# PIN2DMD_Nucleo144.net
KiCad netlist of a schematic drawn in EAGLE
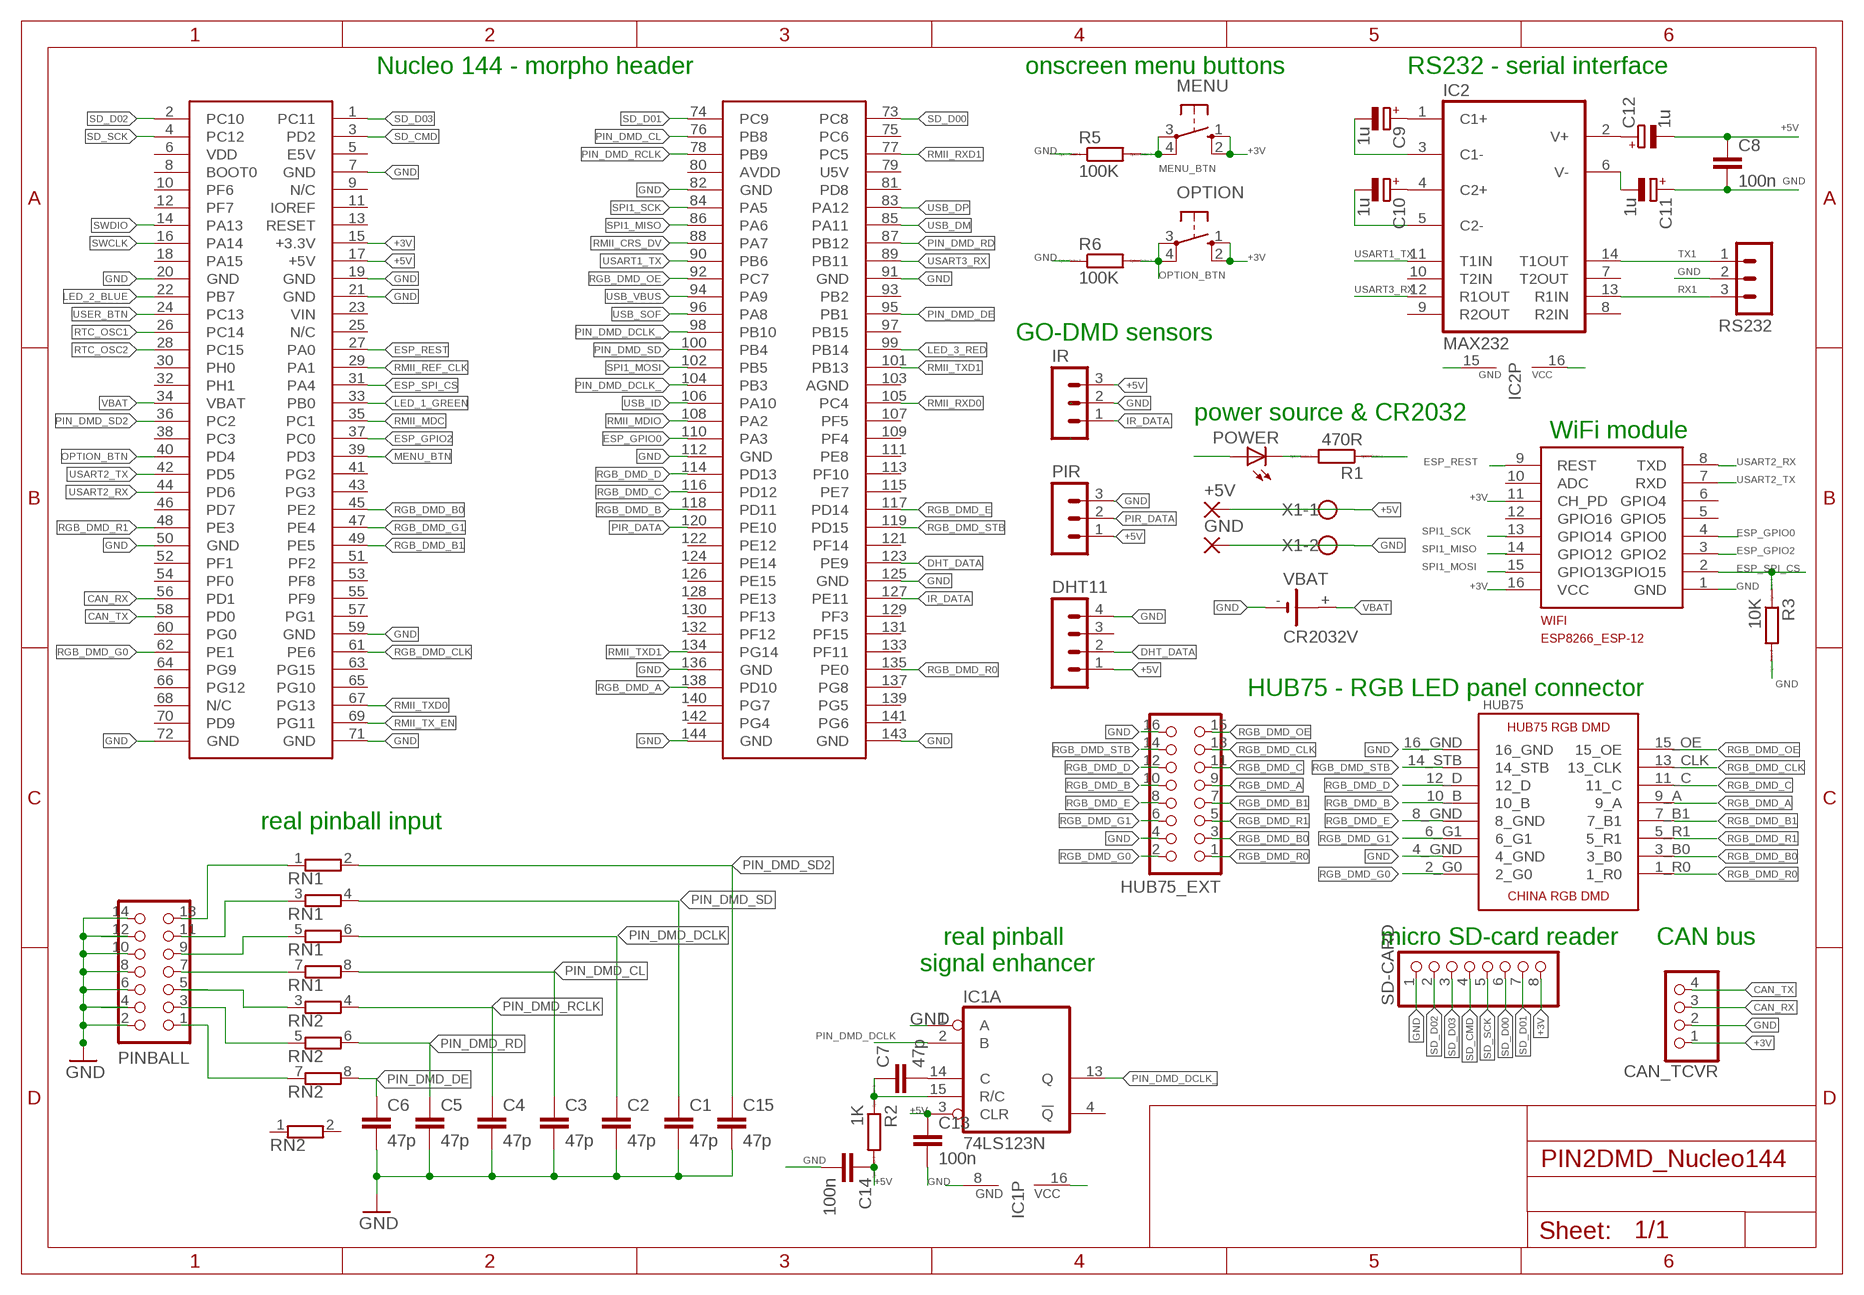
[diagram p0: schematic, sheet 1]

(export (version "E")
  (design (tool "Eeschema 10.0.6"))
  (components
    (comp (ref "+5V")
      (value "WIREPADSMD2,54-5,08")
      (footprint "eagle-import:SMD2,54-5,08")
      (libsource (lib "eagle-import") (part "WIREPADSMD2,54-5,08"))
    )
    (comp (ref "C1")
      (value "47p")
      (footprint "eagle-import:C025-024X044")
      (libsource (lib "eagle-import") (part "C-EU025-024X044"))
    )
    (comp (ref "C2")
      (value "47p")
      (footprint "eagle-import:C025-024X044")
      (libsource (lib "eagle-import") (part "C-EU025-024X044"))
    )
    (comp (ref "C3")
      (value "47p")
      (footprint "eagle-import:C025-024X044")
      (libsource (lib "eagle-import") (part "C-EU025-024X044"))
    )
    (comp (ref "C4")
      (value "47p")
      (footprint "eagle-import:C025-024X044")
      (libsource (lib "eagle-import") (part "C-EU025-024X044"))
    )
    (comp (ref "C5")
      (value "47p")
      (footprint "eagle-import:C025-024X044")
      (libsource (lib "eagle-import") (part "C-EU025-024X044"))
    )
    (comp (ref "C6")
      (value "47p")
      (footprint "eagle-import:C025-024X044")
      (libsource (lib "eagle-import") (part "C-EU025-024X044"))
    )
    (comp (ref "C7")
      (value "47p")
      (footprint "eagle-import:C025-024X044")
      (libsource (lib "eagle-import") (part "C-EU025-024X044"))
    )
    (comp (ref "C8")
      (value "100n")
      (footprint "eagle-import:C025-024X044")
      (libsource (lib "eagle-import") (part "C-EU025-024X044"))
    )
    (comp (ref "C9")
      (value "1u")
      (footprint "eagle-import:E2-4")
      (libsource (lib "eagle-import") (part "CPOL-EUE2-4"))
    )
    (comp (ref "C10")
      (value "1u")
      (footprint "eagle-import:E2-4")
      (libsource (lib "eagle-import") (part "CPOL-EUE2-4"))
    )
    (comp (ref "C11")
      (value "1u")
      (footprint "eagle-import:E2-4")
      (libsource (lib "eagle-import") (part "CPOL-EUE2-4"))
    )
    (comp (ref "C12")
      (value "1u")
      (footprint "eagle-import:E2-4")
      (libsource (lib "eagle-import") (part "CPOL-EUE2-4"))
    )
    (comp (ref "C13")
      (value "100n")
      (footprint "eagle-import:C025-024X044")
      (libsource (lib "eagle-import") (part "C-EU025-024X044"))
    )
    (comp (ref "C14")
      (value "100n")
      (footprint "eagle-import:C025-024X044")
      (libsource (lib "eagle-import") (part "C-EU025-024X044"))
    )
    (comp (ref "C15")
      (value "47p")
      (footprint "eagle-import:C025-024X044")
      (libsource (lib "eagle-import") (part "C-EU025-024X044"))
    )
    (comp (ref "CAN_TCVR")
      (value "PINHD-1X4")
      (footprint "eagle-import:1X04")
      (libsource (lib "eagle-import") (part "PINHD-1X4"))
    )
    (comp (ref "DHT11")
      (value "MA04-1")
      (footprint "eagle-import:MA04-1")
      (libsource (lib "eagle-import") (part "MA04-1"))
    )
    (comp (ref "GND")
      (value "WIREPADSMD2,54-5,08")
      (footprint "eagle-import:SMD2,54-5,08")
      (libsource (lib "eagle-import") (part "WIREPADSMD2,54-5,08"))
    )
    (comp (ref "HUB75")
      (value "RGB_DMD_HUB75_HEADER_FEMALE")
      (footprint "eagle-import:16_PIN_HUB75_RGB_FEMALE_DOWN")
      (libsource (lib "eagle-import") (part "RGB_DMD_HUB75_HEADER_FEMALE"))
    )
    (comp (ref "HUB75_EXT")
      (value "CON_HEADER_2X08B")
      (footprint "eagle-import:PINSHRD_PTH_2X08")
      (libsource (lib "eagle-import") (part "CON_HEADER_2X08B"))
    )
    (comp (ref "IC1")
      (value "74LS123N")
      (footprint "eagle-import:DIL16")
      (libsource (lib "eagle-import") (part "74123NLS"))
    )
    (comp (ref "IC2")
      (value "MAX232")
      (footprint "eagle-import:DIL16")
      (fields (field (name "MF") "MAXIM") (field (name "MPN") "MAX232ACPE+"))
      (libsource (lib "eagle-import") (part "MAX232"))
    )
    (comp (ref "IR")
      (value "MA03-1")
      (footprint "eagle-import:MA03-1")
      (libsource (lib "eagle-import") (part "MA03-1"))
    )
    (comp (ref "MENU")
      (value "10-XX")
      (footprint "eagle-import:B3F-10XX")
      (fields (field (name "MPN") "B3F-1000"))
      (libsource (lib "eagle-import") (part "10-XX"))
    )
    (comp (ref "OPTION")
      (value "10-XX")
      (footprint "eagle-import:B3F-10XX")
      (fields (field (name "MPN") "B3F-1000"))
      (libsource (lib "eagle-import") (part "10-XX"))
    )
    (comp (ref "PINBALL")
      (value "CON_HEADER_2X07-PTH-SHROUDED")
      (footprint "eagle-import:PINSHRD_PTH_2X07")
      (libsource (lib "eagle-import") (part "CON_HEADER_2X07-PTH-SHROUDED"))
    )
    (comp (ref "PIR")
      (value "MA03-1")
      (footprint "eagle-import:MA03-1")
      (libsource (lib "eagle-import") (part "MA03-1"))
    )
    (comp (ref "POWER")
      (value "LED3MM")
      (footprint "eagle-import:LED3MM")
      (libsource (lib "eagle-import") (part "LED3MM"))
    )
    (comp (ref "R1")
      (value "470R")
      (footprint "eagle-import:0207_10")
      (libsource (lib "eagle-import") (part "R0207/10"))
    )
    (comp (ref "R2")
      (value "1K")
      (footprint "eagle-import:0207_10")
      (libsource (lib "eagle-import") (part "R0207/10"))
    )
    (comp (ref "R3")
      (value "10K")
      (footprint "eagle-import:0207_10")
      (libsource (lib "eagle-import") (part "R0207/10"))
    )
    (comp (ref "R5")
      (value "100K")
      (footprint "eagle-import:0207_10")
      (libsource (lib "eagle-import") (part "R0207/10"))
    )
    (comp (ref "R6")
      (value "100K")
      (footprint "eagle-import:0207_10")
      (libsource (lib "eagle-import") (part "R0207/10"))
    )
    (comp (ref "RN1")
      (value "E4RP")
      (footprint "eagle-import:SIL8")
      (libsource (lib "eagle-import") (part "E4RP"))
    )
    (comp (ref "RN2")
      (value "E4RP")
      (footprint "eagle-import:SIL8")
      (libsource (lib "eagle-import") (part "E4RP"))
    )
    (comp (ref "RS232")
      (value "MA03-1")
      (footprint "eagle-import:MA03-1")
      (libsource (lib "eagle-import") (part "MA03-1"))
    )
    (comp (ref "SD-CARD")
      (value "PINHD-1X8")
      (footprint "eagle-import:1X08")
      (libsource (lib "eagle-import") (part "PINHD-1X8"))
    )
    (comp (ref "U$1")
      (value "NUCLEO-144")
      (footprint "eagle-import:NUCLEO-144")
      (libsource (lib "eagle-import") (part "NUCLEO-144"))
    )
    (comp (ref "VBAT")
      (value "CR2032V")
      (footprint "eagle-import:CR2032V")
      (libsource (lib "eagle-import") (part "CR2032V"))
    )
    (comp (ref "WIFI")
      (value "ESP8266_ESP-12")
      (footprint "eagle-import:ESP8266-ESP12")
      (libsource (lib "eagle-import") (part "ESP8266_ESP-12"))
    )
    (comp (ref "X1")
      (value "W237-102")
      (footprint "eagle-import:W237-102")
      (fields (field (name "MPN") "237-102"))
      (libsource (lib "eagle-import") (part "W237-102"))
    )
  )
  (nets
    (net (code "1") (name "+3V") (class "Default")
      (node (ref "CAN_TCVR") (pin "1") (pinfunction "1_1") (pintype "passive"))
      (node (ref "MENU") (pin "1") (pinfunction "S_1") (pintype "passive"))
      (node (ref "MENU") (pin "2") (pinfunction "S1_2") (pintype "passive"))
      (node (ref "OPTION") (pin "1") (pinfunction "S_1") (pintype "passive"))
      (node (ref "OPTION") (pin "2") (pinfunction "S1_2") (pintype "passive"))
      (node (ref "SD-CARD") (pin "8") (pinfunction "8_8") (pintype "passive"))
      (node (ref "U$1") (pin "15") (pinfunction "+3.3V_15") (pintype "bidirectional"))
      (node (ref "WIFI") (pin "11") (pinfunction "CH_PD_11") (pintype "bidirectional"))
      (node (ref "WIFI") (pin "16") (pinfunction "VCC_16") (pintype "bidirectional"))
    )
    (net (code "2") (name "+5V") (class "Default")
      (node (ref "+5V") (pin "1") (pinfunction "P_1") (pintype "passive"))
      (node (ref "C12") (pin "-") (pinfunction "-_-") (pintype "passive"))
      (node (ref "C13") (pin "1") (pinfunction "1_1") (pintype "passive"))
      (node (ref "C14") (pin "1") (pinfunction "1_1") (pintype "passive"))
      (node (ref "C8") (pin "1") (pinfunction "1_1") (pintype "passive"))
      (node (ref "DHT11") (pin "1") (pinfunction "1_1") (pintype "passive"))
      (node (ref "IC1") (pin "16") (pinfunction "VCC_16") (pintype "power_in"))
      (node (ref "IC1") (pin "3") (pinfunction "CLR_3") (pintype "input"))
      (node (ref "IC2") (pin "16") (pinfunction "VCC_16") (pintype "power_in"))
      (node (ref "IR") (pin "3") (pinfunction "3_3") (pintype "passive"))
      (node (ref "PIR") (pin "1") (pinfunction "1_1") (pintype "passive"))
      (node (ref "POWER") (pin "A") (pinfunction "A_A") (pintype "passive"))
      (node (ref "R2") (pin "2") (pinfunction "2_2") (pintype "passive"))
      (node (ref "U$1") (pin "17") (pinfunction "+5V_17") (pintype "bidirectional"))
      (node (ref "X1") (pin "1") (pinfunction "KL_1") (pintype "passive"))
    )
    (net (code "3") (name "/RX1") (class "Default")
      (node (ref "IC2") (pin "13") (pinfunction "R1IN_13") (pintype "input"))
      (node (ref "RS232") (pin "3") (pinfunction "3_3") (pintype "passive"))
    )
    (net (code "4") (name "/TX1") (class "Default")
      (node (ref "IC2") (pin "14") (pinfunction "T1OUT_14") (pintype "output"))
      (node (ref "RS232") (pin "1") (pinfunction "1_1") (pintype "passive"))
    )
    (net (code "5") (name "CAN_RX") (class "Default")
      (node (ref "CAN_TCVR") (pin "3") (pinfunction "3_3") (pintype "passive"))
      (node (ref "U$1") (pin "56") (pinfunction "PD1_56") (pintype "bidirectional"))
    )
    (net (code "6") (name "CAN_TX") (class "Default")
      (node (ref "CAN_TCVR") (pin "4") (pinfunction "4_4") (pintype "passive"))
      (node (ref "U$1") (pin "58") (pinfunction "PD0_58") (pintype "bidirectional"))
    )
    (net (code "7") (name "DHT_DATA") (class "Default")
      (node (ref "DHT11") (pin "2") (pinfunction "2_2") (pintype "passive"))
      (node (ref "U$1") (pin "123") (pinfunction "PE9_123") (pintype "bidirectional"))
    )
    (net (code "8") (name "ESP_GPIO0") (class "Default")
      (node (ref "U$1") (pin "110") (pinfunction "PA3_110") (pintype "bidirectional"))
      (node (ref "WIFI") (pin "4") (pinfunction "GPIO0_4") (pintype "bidirectional"))
    )
    (net (code "9") (name "ESP_GPIO2") (class "Default")
      (node (ref "U$1") (pin "37") (pinfunction "PC0_37") (pintype "bidirectional"))
      (node (ref "WIFI") (pin "3") (pinfunction "GPIO2_3") (pintype "bidirectional"))
    )
    (net (code "10") (name "ESP_REST") (class "Default")
      (node (ref "U$1") (pin "27") (pinfunction "PA0_27") (pintype "bidirectional"))
      (node (ref "WIFI") (pin "9") (pinfunction "REST_9") (pintype "bidirectional"))
    )
    (net (code "11") (name "ESP_SPI_CS") (class "Default")
      (node (ref "R3") (pin "1") (pinfunction "1_1") (pintype "passive"))
      (node (ref "U$1") (pin "31") (pinfunction "PA4_31") (pintype "bidirectional"))
      (node (ref "WIFI") (pin "2") (pinfunction "GPIO15_2") (pintype "bidirectional"))
    )
    (net (code "12") (name "GND") (class "Default")
      (node (ref "C1") (pin "2") (pinfunction "2_2") (pintype "passive"))
      (node (ref "C11") (pin "+") (pinfunction "+_+") (pintype "passive"))
      (node (ref "C13") (pin "2") (pinfunction "2_2") (pintype "passive"))
      (node (ref "C14") (pin "2") (pinfunction "2_2") (pintype "passive"))
      (node (ref "C15") (pin "2") (pinfunction "2_2") (pintype "passive"))
      (node (ref "C2") (pin "2") (pinfunction "2_2") (pintype "passive"))
      (node (ref "C3") (pin "2") (pinfunction "2_2") (pintype "passive"))
      (node (ref "C4") (pin "2") (pinfunction "2_2") (pintype "passive"))
      (node (ref "C5") (pin "2") (pinfunction "2_2") (pintype "passive"))
      (node (ref "C6") (pin "2") (pinfunction "2_2") (pintype "passive"))
      (node (ref "C8") (pin "2") (pinfunction "2_2") (pintype "passive"))
      (node (ref "CAN_TCVR") (pin "2") (pinfunction "2_2") (pintype "passive"))
      (node (ref "DHT11") (pin "4") (pinfunction "4_4") (pintype "passive"))
      (node (ref "GND") (pin "1") (pinfunction "P_1") (pintype "passive"))
      (node (ref "HUB75") (pin "16_GND") (pinfunction "16_GND_16_GND") (pintype "bidirectional"))
      (node (ref "HUB75") (pin "4_GND") (pinfunction "4_GND_4_GND") (pintype "bidirectional"))
      (node (ref "HUB75_EXT") (pin "16") (pinfunction "16_16") (pintype "passive"))
      (node (ref "HUB75_EXT") (pin "4") (pinfunction "4_4") (pintype "passive"))
      (node (ref "IC1") (pin "1") (pinfunction "A_1") (pintype "input"))
      (node (ref "IC1") (pin "8") (pinfunction "GND_8") (pintype "power_in"))
      (node (ref "IC2") (pin "15") (pinfunction "GND_15") (pintype "power_in"))
      (node (ref "IR") (pin "2") (pinfunction "2_2") (pintype "passive"))
      (node (ref "PINBALL") (pin "10") (pinfunction "10_10") (pintype "passive"))
      (node (ref "PINBALL") (pin "12") (pinfunction "12_12") (pintype "passive"))
      (node (ref "PINBALL") (pin "14") (pinfunction "14_14") (pintype "passive"))
      (node (ref "PINBALL") (pin "2") (pinfunction "2_2") (pintype "passive"))
      (node (ref "PINBALL") (pin "4") (pinfunction "4_4") (pintype "passive"))
      (node (ref "PINBALL") (pin "6") (pinfunction "6_6") (pintype "passive"))
      (node (ref "PINBALL") (pin "8") (pinfunction "8_8") (pintype "passive"))
      (node (ref "PIR") (pin "3") (pinfunction "3_3") (pintype "passive"))
      (node (ref "R1") (pin "1") (pinfunction "1_1") (pintype "passive"))
      (node (ref "R3") (pin "2") (pinfunction "2_2") (pintype "passive"))
      (node (ref "R5") (pin "1") (pinfunction "1_1") (pintype "passive"))
      (node (ref "R6") (pin "1") (pinfunction "1_1") (pintype "passive"))
      (node (ref "RS232") (pin "2") (pinfunction "2_2") (pintype "passive"))
      (node (ref "SD-CARD") (pin "1") (pinfunction "1_1") (pintype "passive"))
      (node (ref "U$1") (pin "112") (pinfunction "GND_112") (pintype "bidirectional"))
      (node (ref "U$1") (pin "125") (pinfunction "GND_125") (pintype "bidirectional"))
      (node (ref "U$1") (pin "136") (pinfunction "GND_136") (pintype "bidirectional"))
      (node (ref "U$1") (pin "143") (pinfunction "GND_143") (pintype "bidirectional"))
      (node (ref "U$1") (pin "144") (pinfunction "GND_144") (pintype "bidirectional"))
      (node (ref "U$1") (pin "19") (pinfunction "GND_19") (pintype "bidirectional"))
      (node (ref "U$1") (pin "20") (pinfunction "GND_20") (pintype "bidirectional"))
      (node (ref "U$1") (pin "21") (pinfunction "GND_21") (pintype "bidirectional"))
      (node (ref "U$1") (pin "50") (pinfunction "GND_50") (pintype "bidirectional"))
      (node (ref "U$1") (pin "59") (pinfunction "GND_59") (pintype "bidirectional"))
      (node (ref "U$1") (pin "7") (pinfunction "GND_7") (pintype "bidirectional"))
      (node (ref "U$1") (pin "71") (pinfunction "GND_71") (pintype "bidirectional"))
      (node (ref "U$1") (pin "72") (pinfunction "GND_72") (pintype "bidirectional"))
      (node (ref "U$1") (pin "82") (pinfunction "GND_82") (pintype "bidirectional"))
      (node (ref "U$1") (pin "91") (pinfunction "GND_91") (pintype "bidirectional"))
      (node (ref "VBAT") (pin "-") (pinfunction "-_-") (pintype "passive"))
      (node (ref "WIFI") (pin "1") (pinfunction "GND_1") (pintype "bidirectional"))
      (node (ref "X1") (pin "2") (pinfunction "KL_2") (pintype "passive"))
    )
    (net (code "13") (name "IR_DATA") (class "Default")
      (node (ref "IR") (pin "1") (pinfunction "1_1") (pintype "passive"))
      (node (ref "U$1") (pin "127") (pinfunction "PE11_127") (pintype "bidirectional"))
    )
    (net (code "14") (name "LED_1_GREEN") (class "Default")
      (node (ref "U$1") (pin "33") (pinfunction "PB0_33") (pintype "bidirectional"))
    )
    (net (code "15") (name "LED_2_BLUE") (class "Default")
      (node (ref "U$1") (pin "22") (pinfunction "PB7_22") (pintype "bidirectional"))
    )
    (net (code "16") (name "LED_3_RED") (class "Default")
      (node (ref "U$1") (pin "99") (pinfunction "PB14_99") (pintype "bidirectional"))
    )
    (net (code "17") (name "MENU_BTN") (class "Default")
      (node (ref "MENU") (pin "3") (pinfunction "P_3") (pintype "passive"))
      (node (ref "MENU") (pin "4") (pinfunction "P1_4") (pintype "passive"))
      (node (ref "R5") (pin "2") (pinfunction "2_2") (pintype "passive"))
      (node (ref "U$1") (pin "39") (pinfunction "PD3_39") (pintype "bidirectional"))
    )
    (net (code "18") (name "Net-(IC1A-C)") (class "Default")
      (node (ref "C7") (pin "2") (pinfunction "2_2") (pintype "passive"))
      (node (ref "IC1") (pin "14") (pinfunction "C_14") (pintype "input"))
    )
    (net (code "19") (name "Net-(IC1A-R{slash}C)") (class "Default")
      (node (ref "C7") (pin "1") (pinfunction "1_1") (pintype "passive"))
      (node (ref "IC1") (pin "15") (pinfunction "R/C_15") (pintype "input"))
      (node (ref "R2") (pin "1") (pinfunction "1_1") (pintype "passive"))
    )
    (net (code "20") (name "Net-(IC2A-C1+)") (class "Default")
      (node (ref "C9") (pin "+") (pinfunction "+_+") (pintype "passive"))
      (node (ref "IC2") (pin "1") (pinfunction "C1+_1") (pintype "bidirectional"))
    )
    (net (code "21") (name "Net-(IC2A-C1-)") (class "Default")
      (node (ref "C9") (pin "-") (pinfunction "-_-") (pintype "passive"))
      (node (ref "IC2") (pin "3") (pinfunction "C1-_3") (pintype "bidirectional"))
    )
    (net (code "22") (name "Net-(IC2A-C2+)") (class "Default")
      (node (ref "C10") (pin "+") (pinfunction "+_+") (pintype "passive"))
      (node (ref "IC2") (pin "4") (pinfunction "C2+_4") (pintype "bidirectional"))
    )
    (net (code "23") (name "Net-(IC2A-C2-)") (class "Default")
      (node (ref "C10") (pin "-") (pinfunction "-_-") (pintype "passive"))
      (node (ref "IC2") (pin "5") (pinfunction "C2-_5") (pintype "bidirectional"))
    )
    (net (code "24") (name "Net-(IC2A-V+)") (class "Default")
      (node (ref "C12") (pin "+") (pinfunction "+_+") (pintype "passive"))
      (node (ref "IC2") (pin "2") (pinfunction "V+_2") (pintype "bidirectional"))
    )
    (net (code "25") (name "Net-(IC2A-V-)") (class "Default")
      (node (ref "C11") (pin "-") (pinfunction "-_-") (pintype "passive"))
      (node (ref "IC2") (pin "6") (pinfunction "V-_6") (pintype "bidirectional"))
    )
    (net (code "26") (name "Net-(PINBALL-Pad13)") (class "Default")
      (node (ref "PINBALL") (pin "13") (pinfunction "13_13") (pintype "passive"))
      (node (ref "RN1") (pin "1") (pinfunction "1_1") (pintype "passive"))
    )
    (net (code "27") (name "Net-(POWER-C)") (class "Default")
      (node (ref "POWER") (pin "K") (pinfunction "C_K") (pintype "passive"))
      (node (ref "R1") (pin "2") (pinfunction "2_2") (pintype "passive"))
    )
    (net (code "28") (name "Net-(RN1B-1)") (class "Default")
      (node (ref "PINBALL") (pin "11") (pinfunction "11_11") (pintype "passive"))
      (node (ref "RN1") (pin "3") (pinfunction "1_3") (pintype "passive"))
    )
    (net (code "29") (name "Net-(RN1C-1)") (class "Default")
      (node (ref "PINBALL") (pin "9") (pinfunction "9_9") (pintype "passive"))
      (node (ref "RN1") (pin "5") (pinfunction "1_5") (pintype "passive"))
    )
    (net (code "30") (name "Net-(RN1D-1)") (class "Default")
      (node (ref "PINBALL") (pin "7") (pinfunction "7_7") (pintype "passive"))
      (node (ref "RN1") (pin "7") (pinfunction "1_7") (pintype "passive"))
    )
    (net (code "31") (name "Net-(RN2B-1)") (class "Default")
      (node (ref "PINBALL") (pin "5") (pinfunction "5_5") (pintype "passive"))
      (node (ref "RN2") (pin "3") (pinfunction "1_3") (pintype "passive"))
    )
    (net (code "32") (name "Net-(RN2C-1)") (class "Default")
      (node (ref "PINBALL") (pin "3") (pinfunction "3_3") (pintype "passive"))
      (node (ref "RN2") (pin "5") (pinfunction "1_5") (pintype "passive"))
    )
    (net (code "33") (name "Net-(RN2D-1)") (class "Default")
      (node (ref "PINBALL") (pin "1") (pinfunction "1_1") (pintype "passive"))
      (node (ref "RN2") (pin "7") (pinfunction "1_7") (pintype "passive"))
    )
    (net (code "34") (name "OPTION_BTN") (class "Default")
      (node (ref "OPTION") (pin "3") (pinfunction "P_3") (pintype "passive"))
      (node (ref "OPTION") (pin "4") (pinfunction "P1_4") (pintype "passive"))
      (node (ref "R6") (pin "2") (pinfunction "2_2") (pintype "passive"))
      (node (ref "U$1") (pin "40") (pinfunction "PD4_40") (pintype "bidirectional"))
    )
    (net (code "35") (name "PIN_DMD_CL") (class "Default")
      (node (ref "C3") (pin "1") (pinfunction "1_1") (pintype "passive"))
      (node (ref "RN1") (pin "8") (pinfunction "2_8") (pintype "passive"))
      (node (ref "U$1") (pin "76") (pinfunction "PB8_76") (pintype "bidirectional"))
    )
    (net (code "36") (name "PIN_DMD_DCLK") (class "Default")
      (node (ref "C2") (pin "1") (pinfunction "1_1") (pintype "passive"))
      (node (ref "IC1") (pin "2") (pinfunction "B_2") (pintype "input"))
      (node (ref "RN1") (pin "6") (pinfunction "2_6") (pintype "passive"))
    )
    (net (code "37") (name "PIN_DMD_DCLK_") (class "Default")
      (node (ref "IC1") (pin "13") (pinfunction "Q_13") (pintype "output"))
      (node (ref "U$1") (pin "104") (pinfunction "PB3_104") (pintype "bidirectional"))
      (node (ref "U$1") (pin "98") (pinfunction "PB10_98") (pintype "bidirectional"))
    )
    (net (code "38") (name "PIN_DMD_DE") (class "Default")
      (node (ref "C6") (pin "1") (pinfunction "1_1") (pintype "passive"))
      (node (ref "RN2") (pin "8") (pinfunction "2_8") (pintype "passive"))
      (node (ref "U$1") (pin "95") (pinfunction "PB1_95") (pintype "bidirectional"))
    )
    (net (code "39") (name "PIN_DMD_RCLK") (class "Default")
      (node (ref "C4") (pin "1") (pinfunction "1_1") (pintype "passive"))
      (node (ref "RN2") (pin "4") (pinfunction "2_4") (pintype "passive"))
      (node (ref "U$1") (pin "78") (pinfunction "PB9_78") (pintype "bidirectional"))
    )
    (net (code "40") (name "PIN_DMD_RD") (class "Default")
      (node (ref "C5") (pin "1") (pinfunction "1_1") (pintype "passive"))
      (node (ref "RN2") (pin "6") (pinfunction "2_6") (pintype "passive"))
      (node (ref "U$1") (pin "87") (pinfunction "PB12_87") (pintype "bidirectional"))
    )
    (net (code "41") (name "PIN_DMD_SD") (class "Default")
      (node (ref "C1") (pin "1") (pinfunction "1_1") (pintype "passive"))
      (node (ref "RN1") (pin "4") (pinfunction "2_4") (pintype "passive"))
      (node (ref "U$1") (pin "100") (pinfunction "PB4_100") (pintype "bidirectional"))
    )
    (net (code "42") (name "PIN_DMD_SD2") (class "Default")
      (node (ref "C15") (pin "1") (pinfunction "1_1") (pintype "passive"))
      (node (ref "RN1") (pin "2") (pinfunction "2_2") (pintype "passive"))
      (node (ref "U$1") (pin "36") (pinfunction "PC2_36") (pintype "bidirectional"))
    )
    (net (code "43") (name "PIR_DATA") (class "Default")
      (node (ref "PIR") (pin "2") (pinfunction "2_2") (pintype "passive"))
      (node (ref "U$1") (pin "120") (pinfunction "PE10_120") (pintype "bidirectional"))
    )
    (net (code "44") (name "RGB_DMD_A") (class "Default")
      (node (ref "HUB75") (pin "9_A") (pinfunction "9_A_9_A") (pintype "bidirectional"))
      (node (ref "HUB75_EXT") (pin "9") (pinfunction "9_9") (pintype "passive"))
      (node (ref "U$1") (pin "138") (pinfunction "PD10_138") (pintype "bidirectional"))
    )
    (net (code "45") (name "RGB_DMD_B") (class "Default")
      (node (ref "HUB75") (pin "10_B") (pinfunction "10_B_10_B") (pintype "bidirectional"))
      (node (ref "HUB75_EXT") (pin "10") (pinfunction "10_10") (pintype "passive"))
      (node (ref "U$1") (pin "118") (pinfunction "PD11_118") (pintype "bidirectional"))
    )
    (net (code "46") (name "RGB_DMD_B0") (class "Default")
      (node (ref "HUB75") (pin "3_B0") (pinfunction "3_B0_3_B0") (pintype "bidirectional"))
      (node (ref "HUB75_EXT") (pin "3") (pinfunction "3_3") (pintype "passive"))
      (node (ref "U$1") (pin "45") (pinfunction "PE2_45") (pintype "bidirectional"))
    )
    (net (code "47") (name "RGB_DMD_B1") (class "Default")
      (node (ref "HUB75") (pin "7_B1") (pinfunction "7_B1_7_B1") (pintype "bidirectional"))
      (node (ref "HUB75_EXT") (pin "7") (pinfunction "7_7") (pintype "passive"))
      (node (ref "U$1") (pin "49") (pinfunction "PE5_49") (pintype "bidirectional"))
    )
    (net (code "48") (name "RGB_DMD_C") (class "Default")
      (node (ref "HUB75") (pin "11_C") (pinfunction "11_C_11_C") (pintype "bidirectional"))
      (node (ref "HUB75_EXT") (pin "11") (pinfunction "11_11") (pintype "passive"))
      (node (ref "U$1") (pin "116") (pinfunction "PD12_116") (pintype "bidirectional"))
    )
    (net (code "49") (name "RGB_DMD_CLK") (class "Default")
      (node (ref "HUB75") (pin "13_CLK") (pinfunction "13_CLK_13_CLK") (pintype "bidirectional"))
      (node (ref "HUB75_EXT") (pin "13") (pinfunction "13_13") (pintype "passive"))
      (node (ref "U$1") (pin "61") (pinfunction "PE6_61") (pintype "bidirectional"))
    )
    (net (code "50") (name "RGB_DMD_D") (class "Default")
      (node (ref "HUB75") (pin "12_D") (pinfunction "12_D_12_D") (pintype "bidirectional"))
      (node (ref "HUB75_EXT") (pin "12") (pinfunction "12_12") (pintype "passive"))
      (node (ref "U$1") (pin "114") (pinfunction "PD13_114") (pintype "bidirectional"))
    )
    (net (code "51") (name "RGB_DMD_E") (class "Default")
      (node (ref "HUB75") (pin "8_GND") (pinfunction "8_GND_8_GND") (pintype "bidirectional"))
      (node (ref "HUB75_EXT") (pin "8") (pinfunction "8_8") (pintype "passive"))
      (node (ref "U$1") (pin "117") (pinfunction "PD14_117") (pintype "bidirectional"))
    )
    (net (code "52") (name "RGB_DMD_G0") (class "Default")
      (node (ref "HUB75") (pin "2_G0") (pinfunction "2_G0_2_G0") (pintype "bidirectional"))
      (node (ref "HUB75_EXT") (pin "2") (pinfunction "2_2") (pintype "passive"))
      (node (ref "U$1") (pin "62") (pinfunction "PE1_62") (pintype "bidirectional"))
    )
    (net (code "53") (name "RGB_DMD_G1") (class "Default")
      (node (ref "HUB75") (pin "6_G1") (pinfunction "6_G1_6_G1") (pintype "bidirectional"))
      (node (ref "HUB75_EXT") (pin "6") (pinfunction "6_6") (pintype "passive"))
      (node (ref "U$1") (pin "47") (pinfunction "PE4_47") (pintype "bidirectional"))
    )
    (net (code "54") (name "RGB_DMD_OE") (class "Default")
      (node (ref "HUB75") (pin "15_OE") (pinfunction "15_OE_15_OE") (pintype "bidirectional"))
      (node (ref "HUB75_EXT") (pin "15") (pinfunction "15_15") (pintype "passive"))
      (node (ref "U$1") (pin "92") (pinfunction "PC7_92") (pintype "bidirectional"))
    )
    (net (code "55") (name "RGB_DMD_R0") (class "Default")
      (node (ref "HUB75") (pin "1_R0") (pinfunction "1_R0_1_R0") (pintype "bidirectional"))
      (node (ref "HUB75_EXT") (pin "1") (pinfunction "1_1") (pintype "passive"))
      (node (ref "U$1") (pin "135") (pinfunction "PE0_135") (pintype "bidirectional"))
    )
    (net (code "56") (name "RGB_DMD_R1") (class "Default")
      (node (ref "HUB75") (pin "5_R1") (pinfunction "5_R1_5_R1") (pintype "bidirectional"))
      (node (ref "HUB75_EXT") (pin "5") (pinfunction "5_5") (pintype "passive"))
      (node (ref "U$1") (pin "48") (pinfunction "PE3_48") (pintype "bidirectional"))
    )
    (net (code "57") (name "RGB_DMD_STB") (class "Default")
      (node (ref "HUB75") (pin "14_STB") (pinfunction "14_STB_14_STB") (pintype "bidirectional"))
      (node (ref "HUB75_EXT") (pin "14") (pinfunction "14_14") (pintype "passive"))
      (node (ref "U$1") (pin "119") (pinfunction "PD15_119") (pintype "bidirectional"))
    )
    (net (code "58") (name "RMII_CRS_DV") (class "Default")
      (node (ref "U$1") (pin "88") (pinfunction "PA7_88") (pintype "bidirectional"))
    )
    (net (code "59") (name "RMII_MDC") (class "Default")
      (node (ref "U$1") (pin "35") (pinfunction "PC1_35") (pintype "bidirectional"))
    )
    (net (code "60") (name "RMII_MDIO") (class "Default")
      (node (ref "U$1") (pin "108") (pinfunction "PA2_108") (pintype "bidirectional"))
    )
    (net (code "61") (name "RMII_REF_CLK") (class "Default")
      (node (ref "U$1") (pin "29") (pinfunction "PA1_29") (pintype "bidirectional"))
    )
    (net (code "62") (name "RMII_RXD0") (class "Default")
      (node (ref "U$1") (pin "105") (pinfunction "PC4_105") (pintype "bidirectional"))
    )
    (net (code "63") (name "RMII_RXD1") (class "Default")
      (node (ref "U$1") (pin "77") (pinfunction "PC5_77") (pintype "bidirectional"))
    )
    (net (code "64") (name "RMII_TXD0") (class "Default")
      (node (ref "U$1") (pin "67") (pinfunction "PG13_67") (pintype "bidirectional"))
    )
    (net (code "65") (name "RMII_TXD1") (class "Default")
      (node (ref "U$1") (pin "101") (pinfunction "PB13_101") (pintype "bidirectional"))
      (node (ref "U$1") (pin "134") (pinfunction "PG14_134") (pintype "bidirectional"))
    )
    (net (code "66") (name "RMII_TX_EN") (class "Default")
      (node (ref "U$1") (pin "69") (pinfunction "PG11_69") (pintype "bidirectional"))
    )
    (net (code "67") (name "RTC_OSC1") (class "Default")
      (node (ref "U$1") (pin "26") (pinfunction "PC14_26") (pintype "bidirectional"))
    )
    (net (code "68") (name "RTC_OSC2") (class "Default")
      (node (ref "U$1") (pin "28") (pinfunction "PC15_28") (pintype "bidirectional"))
    )
    (net (code "69") (name "SD_CMD") (class "Default")
      (node (ref "SD-CARD") (pin "4") (pinfunction "4_4") (pintype "passive"))
      (node (ref "U$1") (pin "3") (pinfunction "PD2_3") (pintype "bidirectional"))
    )
    (net (code "70") (name "SD_D00") (class "Default")
      (node (ref "SD-CARD") (pin "6") (pinfunction "6_6") (pintype "passive"))
      (node (ref "U$1") (pin "73") (pinfunction "PC8_73") (pintype "bidirectional"))
    )
    (net (code "71") (name "SD_D01") (class "Default")
      (node (ref "SD-CARD") (pin "7") (pinfunction "7_7") (pintype "passive"))
      (node (ref "U$1") (pin "74") (pinfunction "PC9_74") (pintype "bidirectional"))
    )
    (net (code "72") (name "SD_D02") (class "Default")
      (node (ref "SD-CARD") (pin "2") (pinfunction "2_2") (pintype "passive"))
      (node (ref "U$1") (pin "2") (pinfunction "PC10_2") (pintype "bidirectional"))
    )
    (net (code "73") (name "SD_D03") (class "Default")
      (node (ref "SD-CARD") (pin "3") (pinfunction "3_3") (pintype "passive"))
      (node (ref "U$1") (pin "1") (pinfunction "PC11_1") (pintype "bidirectional"))
    )
    (net (code "74") (name "SD_SCK") (class "Default")
      (node (ref "SD-CARD") (pin "5") (pinfunction "5_5") (pintype "passive"))
      (node (ref "U$1") (pin "4") (pinfunction "PC12_4") (pintype "bidirectional"))
    )
    (net (code "75") (name "SPI1_MISO") (class "Default")
      (node (ref "U$1") (pin "86") (pinfunction "PA6_86") (pintype "bidirectional"))
      (node (ref "WIFI") (pin "14") (pinfunction "GPIO12_14") (pintype "bidirectional"))
    )
    (net (code "76") (name "SPI1_MOSI") (class "Default")
      (node (ref "U$1") (pin "102") (pinfunction "PB5_102") (pintype "bidirectional"))
      (node (ref "WIFI") (pin "15") (pinfunction "GPIO13_15") (pintype "bidirectional"))
    )
    (net (code "77") (name "SPI1_SCK") (class "Default")
      (node (ref "U$1") (pin "84") (pinfunction "PA5_84") (pintype "bidirectional"))
      (node (ref "WIFI") (pin "13") (pinfunction "GPIO14_13") (pintype "bidirectional"))
    )
    (net (code "78") (name "SWCLK") (class "Default")
      (node (ref "U$1") (pin "16") (pinfunction "PA14_16") (pintype "bidirectional"))
    )
    (net (code "79") (name "SWDIO") (class "Default")
      (node (ref "U$1") (pin "14") (pinfunction "PA13_14") (pintype "bidirectional"))
    )
    (net (code "80") (name "USART1_TX") (class "Default")
      (node (ref "IC2") (pin "11") (pinfunction "T1IN_11") (pintype "input"))
      (node (ref "U$1") (pin "90") (pinfunction "PB6_90") (pintype "bidirectional"))
    )
    (net (code "81") (name "USART2_RX") (class "Default")
      (node (ref "U$1") (pin "44") (pinfunction "PD6_44") (pintype "bidirectional"))
      (node (ref "WIFI") (pin "8") (pinfunction "TXD_8") (pintype "bidirectional"))
    )
    (net (code "82") (name "USART2_TX") (class "Default")
      (node (ref "U$1") (pin "42") (pinfunction "PD5_42") (pintype "bidirectional"))
      (node (ref "WIFI") (pin "7") (pinfunction "RXD_7") (pintype "bidirectional"))
    )
    (net (code "83") (name "USART3_RX") (class "Default")
      (node (ref "IC2") (pin "12") (pinfunction "R1OUT_12") (pintype "output"))
      (node (ref "U$1") (pin "89") (pinfunction "PB11_89") (pintype "bidirectional"))
    )
    (net (code "84") (name "USB_DM") (class "Default")
      (node (ref "U$1") (pin "85") (pinfunction "PA11_85") (pintype "bidirectional"))
    )
    (net (code "85") (name "USB_DP") (class "Default")
      (node (ref "U$1") (pin "83") (pinfunction "PA12_83") (pintype "bidirectional"))
    )
    (net (code "86") (name "USB_ID") (class "Default")
      (node (ref "U$1") (pin "106") (pinfunction "PA10_106") (pintype "bidirectional"))
    )
    (net (code "87") (name "USB_SOF") (class "Default")
      (node (ref "U$1") (pin "96") (pinfunction "PA8_96") (pintype "bidirectional"))
    )
    (net (code "88") (name "USB_VBUS") (class "Default")
      (node (ref "U$1") (pin "94") (pinfunction "PA9_94") (pintype "bidirectional"))
    )
    (net (code "89") (name "USER_BTN") (class "Default")
      (node (ref "U$1") (pin "24") (pinfunction "PC13_24") (pintype "bidirectional"))
    )
    (net (code "90") (name "VBAT") (class "Default")
      (node (ref "U$1") (pin "34") (pinfunction "VBAT_34") (pintype "bidirectional"))
      (node (ref "VBAT") (pin "+") (pinfunction "+_+") (pintype "passive"))
    )
    (net (code "91") (name "unconnected-(DHT11-Pad3)") (class "Default")
      (node (ref "DHT11") (pin "3") (pinfunction "3_3") (pintype "passive"))
    )
    (net (code "92") (name "unconnected-(IC1A-~{Q}-Pad4)") (class "Default")
      (node (ref "IC1") (pin "4") (pinfunction "~{Q}_4") (pintype "output"))
    )
    (net (code "93") (name "unconnected-(IC2A-R2IN-Pad8)") (class "Default")
      (node (ref "IC2") (pin "8") (pinfunction "R2IN_8") (pintype "input"))
    )
    (net (code "94") (name "unconnected-(IC2A-R2OUT-Pad9)") (class "Default")
      (node (ref "IC2") (pin "9") (pinfunction "R2OUT_9") (pintype "output"))
    )
    (net (code "95") (name "unconnected-(IC2A-T2IN-Pad10)") (class "Default")
      (node (ref "IC2") (pin "10") (pinfunction "T2IN_10") (pintype "input"))
    )
    (net (code "96") (name "unconnected-(IC2A-T2OUT-Pad7)") (class "Default")
      (node (ref "IC2") (pin "7") (pinfunction "T2OUT_7") (pintype "output"))
    )
    (net (code "97") (name "unconnected-(RN2-Pad1)") (class "Default")
      (node (ref "RN2") (pin "1") (pinfunction "1_1") (pintype "passive"))
    )
    (net (code "98") (name "unconnected-(RN2-Pad2)") (class "Default")
      (node (ref "RN2") (pin "2") (pinfunction "2_2") (pintype "passive"))
    )
    (net (code "99") (name "unconnected-(U$1-AGND-Pad103)") (class "Default")
      (node (ref "U$1") (pin "103") (pinfunction "AGND_103") (pintype "bidirectional"))
    )
    (net (code "100") (name "unconnected-(U$1-AVDD-Pad80)") (class "Default")
      (node (ref "U$1") (pin "80") (pinfunction "AVDD_80") (pintype "bidirectional"))
    )
    (net (code "101") (name "unconnected-(U$1-BOOT0-Pad8)") (class "Default")
      (node (ref "U$1") (pin "8") (pinfunction "BOOT0_8") (pintype "bidirectional"))
    )
    (net (code "102") (name "unconnected-(U$1-E5V-Pad5)") (class "Default")
      (node (ref "U$1") (pin "5") (pinfunction "E5V_5") (pintype "bidirectional"))
    )
    (net (code "103") (name "unconnected-(U$1-IOREF-Pad11)") (class "Default")
      (node (ref "U$1") (pin "11") (pinfunction "IOREF_11") (pintype "bidirectional"))
    )
    (net (code "104") (name "unconnected-(U$1-N{slash}C-Pad9)") (class "Default")
      (node (ref "U$1") (pin "9") (pinfunction "N/C_9") (pintype "bidirectional"))
    )
    (net (code "105") (name "unconnected-(U$1-N{slash}C-Pad25)") (class "Default")
      (node (ref "U$1") (pin "25") (pinfunction "N/C_25") (pintype "bidirectional"))
    )
    (net (code "106") (name "unconnected-(U$1-N{slash}C-Pad68)") (class "Default")
      (node (ref "U$1") (pin "68") (pinfunction "N/C_68") (pintype "bidirectional"))
    )
    (net (code "107") (name "unconnected-(U$1-PA15-Pad18)") (class "Default")
      (node (ref "U$1") (pin "18") (pinfunction "PA15_18") (pintype "bidirectional"))
    )
    (net (code "108") (name "unconnected-(U$1-PB2-Pad93)") (class "Default")
      (node (ref "U$1") (pin "93") (pinfunction "PB2_93") (pintype "bidirectional"))
    )
    (net (code "109") (name "unconnected-(U$1-PB15-Pad97)") (class "Default")
      (node (ref "U$1") (pin "97") (pinfunction "PB15_97") (pintype "bidirectional"))
    )
    (net (code "110") (name "unconnected-(U$1-PC3-Pad38)") (class "Default")
      (node (ref "U$1") (pin "38") (pinfunction "PC3_38") (pintype "bidirectional"))
    )
    (net (code "111") (name "unconnected-(U$1-PC6-Pad75)") (class "Default")
      (node (ref "U$1") (pin "75") (pinfunction "PC6_75") (pintype "bidirectional"))
    )
    (net (code "112") (name "unconnected-(U$1-PD7-Pad46)") (class "Default")
      (node (ref "U$1") (pin "46") (pinfunction "PD7_46") (pintype "bidirectional"))
    )
    (net (code "113") (name "unconnected-(U$1-PD8-Pad81)") (class "Default")
      (node (ref "U$1") (pin "81") (pinfunction "PD8_81") (pintype "bidirectional"))
    )
    (net (code "114") (name "unconnected-(U$1-PD9-Pad70)") (class "Default")
      (node (ref "U$1") (pin "70") (pinfunction "PD9_70") (pintype "bidirectional"))
    )
    (net (code "115") (name "unconnected-(U$1-PE7-Pad115)") (class "Default")
      (node (ref "U$1") (pin "115") (pinfunction "PE7_115") (pintype "bidirectional"))
    )
    (net (code "116") (name "unconnected-(U$1-PE8-Pad111)") (class "Default")
      (node (ref "U$1") (pin "111") (pinfunction "PE8_111") (pintype "bidirectional"))
    )
    (net (code "117") (name "unconnected-(U$1-PE12-Pad122)") (class "Default")
      (node (ref "U$1") (pin "122") (pinfunction "PE12_122") (pintype "bidirectional"))
    )
    (net (code "118") (name "unconnected-(U$1-PE13-Pad128)") (class "Default")
      (node (ref "U$1") (pin "128") (pinfunction "PE13_128") (pintype "bidirectional"))
    )
    (net (code "119") (name "unconnected-(U$1-PE14-Pad124)") (class "Default")
      (node (ref "U$1") (pin "124") (pinfunction "PE14_124") (pintype "bidirectional"))
    )
    (net (code "120") (name "unconnected-(U$1-PE15-Pad126)") (class "Default")
      (node (ref "U$1") (pin "126") (pinfunction "PE15_126") (pintype "bidirectional"))
    )
    (net (code "121") (name "unconnected-(U$1-PF0-Pad54)") (class "Default")
      (node (ref "U$1") (pin "54") (pinfunction "PF0_54") (pintype "bidirectional"))
    )
    (net (code "122") (name "unconnected-(U$1-PF1-Pad52)") (class "Default")
      (node (ref "U$1") (pin "52") (pinfunction "PF1_52") (pintype "bidirectional"))
    )
    (net (code "123") (name "unconnected-(U$1-PF2-Pad51)") (class "Default")
      (node (ref "U$1") (pin "51") (pinfunction "PF2_51") (pintype "bidirectional"))
    )
    (net (code "124") (name "unconnected-(U$1-PF3-Pad129)") (class "Default")
      (node (ref "U$1") (pin "129") (pinfunction "PF3_129") (pintype "bidirectional"))
    )
    (net (code "125") (name "unconnected-(U$1-PF4-Pad109)") (class "Default")
      (node (ref "U$1") (pin "109") (pinfunction "PF4_109") (pintype "bidirectional"))
    )
    (net (code "126") (name "unconnected-(U$1-PF5-Pad107)") (class "Default")
      (node (ref "U$1") (pin "107") (pinfunction "PF5_107") (pintype "bidirectional"))
    )
    (net (code "127") (name "unconnected-(U$1-PF6-Pad10)") (class "Default")
      (node (ref "U$1") (pin "10") (pinfunction "PF6_10") (pintype "bidirectional"))
    )
    (net (code "128") (name "unconnected-(U$1-PF7-Pad12)") (class "Default")
      (node (ref "U$1") (pin "12") (pinfunction "PF7_12") (pintype "bidirectional"))
    )
    (net (code "129") (name "unconnected-(U$1-PF8-Pad53)") (class "Default")
      (node (ref "U$1") (pin "53") (pinfunction "PF8_53") (pintype "bidirectional"))
    )
    (net (code "130") (name "unconnected-(U$1-PF9-Pad55)") (class "Default")
      (node (ref "U$1") (pin "55") (pinfunction "PF9_55") (pintype "bidirectional"))
    )
    (net (code "131") (name "unconnected-(U$1-PF10-Pad113)") (class "Default")
      (node (ref "U$1") (pin "113") (pinfunction "PF10_113") (pintype "bidirectional"))
    )
    (net (code "132") (name "unconnected-(U$1-PF11-Pad133)") (class "Default")
      (node (ref "U$1") (pin "133") (pinfunction "PF11_133") (pintype "bidirectional"))
    )
    (net (code "133") (name "unconnected-(U$1-PF12-Pad132)") (class "Default")
      (node (ref "U$1") (pin "132") (pinfunction "PF12_132") (pintype "bidirectional"))
    )
    (net (code "134") (name "unconnected-(U$1-PF13-Pad130)") (class "Default")
      (node (ref "U$1") (pin "130") (pinfunction "PF13_130") (pintype "bidirectional"))
    )
    (net (code "135") (name "unconnected-(U$1-PF14-Pad121)") (class "Default")
      (node (ref "U$1") (pin "121") (pinfunction "PF14_121") (pintype "bidirectional"))
    )
    (net (code "136") (name "unconnected-(U$1-PF15-Pad131)") (class "Default")
      (node (ref "U$1") (pin "131") (pinfunction "PF15_131") (pintype "bidirectional"))
    )
    (net (code "137") (name "unconnected-(U$1-PG0-Pad60)") (class "Default")
      (node (ref "U$1") (pin "60") (pinfunction "PG0_60") (pintype "bidirectional"))
    )
    (net (code "138") (name "unconnected-(U$1-PG1-Pad57)") (class "Default")
      (node (ref "U$1") (pin "57") (pinfunction "PG1_57") (pintype "bidirectional"))
    )
    (net (code "139") (name "unconnected-(U$1-PG2-Pad41)") (class "Default")
      (node (ref "U$1") (pin "41") (pinfunction "PG2_41") (pintype "bidirectional"))
    )
    (net (code "140") (name "unconnected-(U$1-PG3-Pad43)") (class "Default")
      (node (ref "U$1") (pin "43") (pinfunction "PG3_43") (pintype "bidirectional"))
    )
    (net (code "141") (name "unconnected-(U$1-PG4-Pad142)") (class "Default")
      (node (ref "U$1") (pin "142") (pinfunction "PG4_142") (pintype "bidirectional"))
    )
    (net (code "142") (name "unconnected-(U$1-PG5-Pad139)") (class "Default")
      (node (ref "U$1") (pin "139") (pinfunction "PG5_139") (pintype "bidirectional"))
    )
    (net (code "143") (name "unconnected-(U$1-PG6-Pad141)") (class "Default")
      (node (ref "U$1") (pin "141") (pinfunction "PG6_141") (pintype "bidirectional"))
    )
    (net (code "144") (name "unconnected-(U$1-PG7-Pad140)") (class "Default")
      (node (ref "U$1") (pin "140") (pinfunction "PG7_140") (pintype "bidirectional"))
    )
    (net (code "145") (name "unconnected-(U$1-PG8-Pad137)") (class "Default")
      (node (ref "U$1") (pin "137") (pinfunction "PG8_137") (pintype "bidirectional"))
    )
    (net (code "146") (name "unconnected-(U$1-PG9-Pad64)") (class "Default")
      (node (ref "U$1") (pin "64") (pinfunction "PG9_64") (pintype "bidirectional"))
    )
    (net (code "147") (name "unconnected-(U$1-PG10-Pad65)") (class "Default")
      (node (ref "U$1") (pin "65") (pinfunction "PG10_65") (pintype "bidirectional"))
    )
    (net (code "148") (name "unconnected-(U$1-PG12-Pad66)") (class "Default")
      (node (ref "U$1") (pin "66") (pinfunction "PG12_66") (pintype "bidirectional"))
    )
    (net (code "149") (name "unconnected-(U$1-PG15-Pad63)") (class "Default")
      (node (ref "U$1") (pin "63") (pinfunction "PG15_63") (pintype "bidirectional"))
    )
    (net (code "150") (name "unconnected-(U$1-PH0-Pad30)") (class "Default")
      (node (ref "U$1") (pin "30") (pinfunction "PH0_30") (pintype "bidirectional"))
    )
    (net (code "151") (name "unconnected-(U$1-PH1-Pad32)") (class "Default")
      (node (ref "U$1") (pin "32") (pinfunction "PH1_32") (pintype "bidirectional"))
    )
    (net (code "152") (name "unconnected-(U$1-RESET-Pad13)") (class "Default")
      (node (ref "U$1") (pin "13") (pinfunction "RESET_13") (pintype "bidirectional"))
    )
    (net (code "153") (name "unconnected-(U$1-U5V-Pad79)") (class "Default")
      (node (ref "U$1") (pin "79") (pinfunction "U5V_79") (pintype "bidirectional"))
    )
    (net (code "154") (name "unconnected-(U$1-VDD-Pad6)") (class "Default")
      (node (ref "U$1") (pin "6") (pinfunction "VDD_6") (pintype "bidirectional"))
    )
    (net (code "155") (name "unconnected-(U$1-VIN-Pad23)") (class "Default")
      (node (ref "U$1") (pin "23") (pinfunction "VIN_23") (pintype "bidirectional"))
    )
    (net (code "156") (name "unconnected-(VBAT-+-Pad+@1)") (class "Default")
      (node (ref "VBAT") (pin "+@1") (pinfunction "+_+@1") (pintype "passive"))
    )
    (net (code "157") (name "unconnected-(WIFI-ADC-Pad10)") (class "Default")
      (node (ref "WIFI") (pin "10") (pinfunction "ADC_10") (pintype "bidirectional"))
    )
    (net (code "158") (name "unconnected-(WIFI-GPIO4-Pad6)") (class "Default")
      (node (ref "WIFI") (pin "6") (pinfunction "GPIO4_6") (pintype "bidirectional"))
    )
    (net (code "159") (name "unconnected-(WIFI-GPIO5-Pad5)") (class "Default")
      (node (ref "WIFI") (pin "5") (pinfunction "GPIO5_5") (pintype "bidirectional"))
    )
    (net (code "160") (name "unconnected-(WIFI-GPIO16-Pad12)") (class "Default")
      (node (ref "WIFI") (pin "12") (pinfunction "GPIO16_12") (pintype "bidirectional"))
    )
  )
)
